# nixie.net
KiCad netlist of a schematic drawn in EAGLE
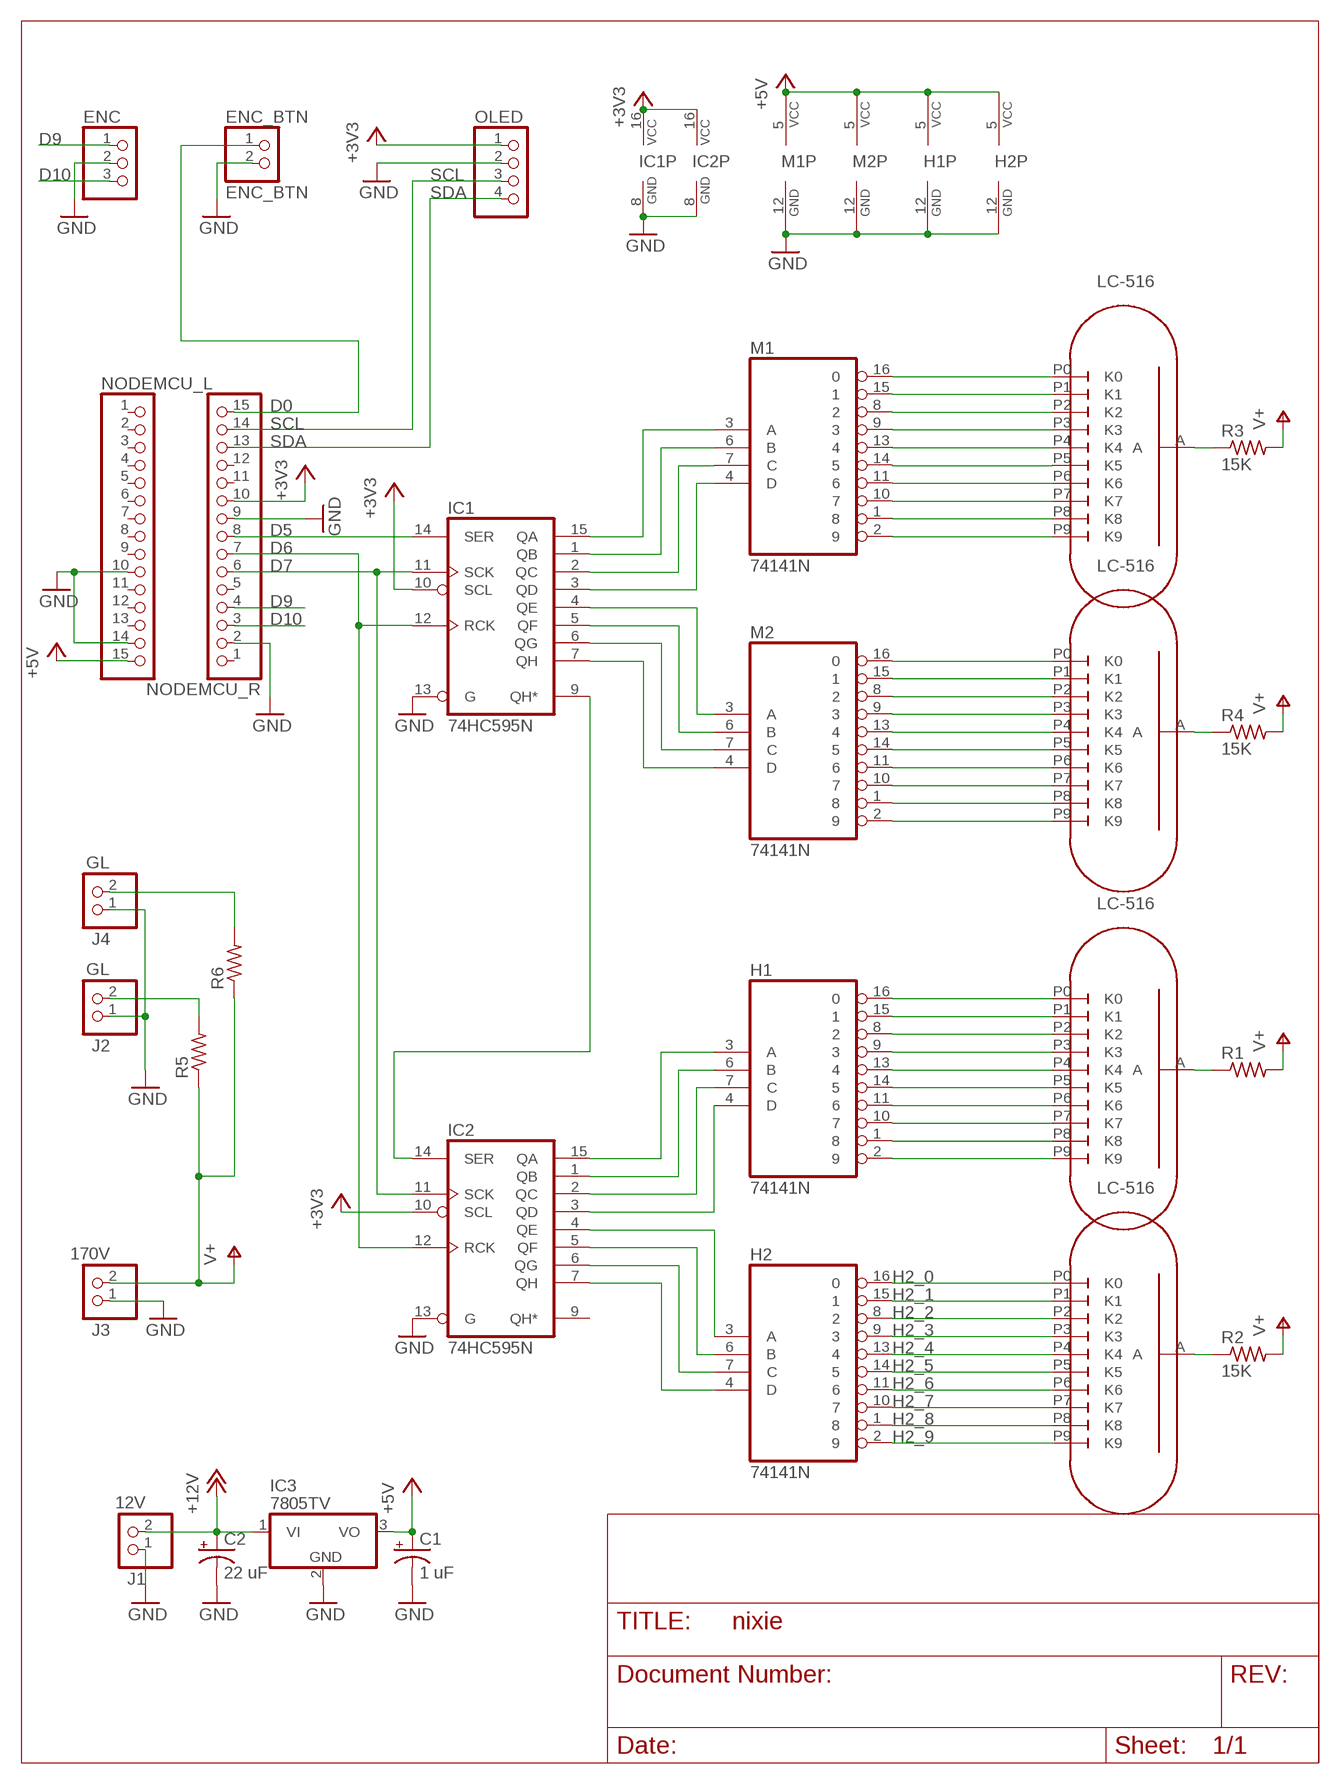
[diagram p0: schematic, sheet 1]

(export (version "E")
  (design (tool "Eeschema 10.0.6"))
  (components
    (comp (ref "C1")
      (value "1 uF")
      (footprint "eagle-import:TT2D5")
      (libsource (lib "eagle-import") (part "CPOL-USTT2D5"))
    )
    (comp (ref "C2")
      (value "22 uF")
      (footprint "eagle-import:TT2D5")
      (libsource (lib "eagle-import") (part "CPOL-USTT2D5"))
    )
    (comp (ref "ENC")
      (value "PINHD-1X3")
      (footprint "eagle-import:1X03")
      (libsource (lib "eagle-import") (part "PINHD-1X3"))
    )
    (comp (ref "ENC_BTN")
      (value "ENC_BTN")
      (footprint "eagle-import:1X02")
      (libsource (lib "eagle-import") (part "PINHD-1X2"))
    )
    (comp (ref "H1")
      (value "74141N")
      (footprint "eagle-import:DIL16")
      (libsource (lib "eagle-import") (part "74141N"))
    )
    (comp (ref "H2")
      (value "74141N")
      (footprint "eagle-import:DIL16")
      (libsource (lib "eagle-import") (part "74141N"))
    )
    (comp (ref "IC1")
      (value "74HC595N")
      (footprint "eagle-import:DIL16")
      (libsource (lib "eagle-import") (part "74595NHC"))
    )
    (comp (ref "IC2")
      (value "74HC595N")
      (footprint "eagle-import:DIL16")
      (libsource (lib "eagle-import") (part "74595NHC"))
    )
    (comp (ref "IC3")
      (value "7805TV")
      (footprint "eagle-import:TO220V")
      (libsource (lib "eagle-import") (part "78TV05"))
    )
    (comp (ref "J1")
      (value "12V")
      (footprint "eagle-import:1X02")
      (libsource (lib "eagle-import") (part "PINHD-1X2"))
    )
    (comp (ref "J2")
      (value "GL")
      (footprint "eagle-import:1X02")
      (libsource (lib "eagle-import") (part "PINHD-1X2"))
    )
    (comp (ref "J3")
      (value "170V")
      (footprint "eagle-import:1X02")
      (libsource (lib "eagle-import") (part "PINHD-1X2"))
    )
    (comp (ref "J4")
      (value "GL")
      (footprint "eagle-import:1X02")
      (libsource (lib "eagle-import") (part "PINHD-1X2"))
    )
    (comp (ref "M1")
      (value "74141N")
      (footprint "eagle-import:DIL16")
      (libsource (lib "eagle-import") (part "74141N"))
    )
    (comp (ref "M2")
      (value "74141N")
      (footprint "eagle-import:DIL16")
      (libsource (lib "eagle-import") (part "74141N"))
    )
    (comp (ref "NODEMCU_L")
      (value "PINHD-1X15")
      (footprint "eagle-import:1X15")
      (libsource (lib "eagle-import") (part "PINHD-1X15"))
    )
    (comp (ref "NODEMCU_R")
      (value "PINHD-1X15")
      (footprint "eagle-import:1X15")
      (libsource (lib "eagle-import") (part "PINHD-1X15"))
    )
    (comp (ref "OLED")
      (value "PINHD-1X4")
      (footprint "eagle-import:1X04")
      (libsource (lib "eagle-import") (part "PINHD-1X4"))
    )
    (comp (ref "R1")
      (value "15K")
      (footprint "eagle-import:0207_10")
      (libsource (lib "eagle-import") (part "R-US_0207/10"))
    )
    (comp (ref "R2")
      (value "15K")
      (footprint "eagle-import:0207_10")
      (libsource (lib "eagle-import") (part "R-US_0207/10"))
    )
    (comp (ref "R3")
      (value "15K")
      (footprint "eagle-import:0207_10")
      (libsource (lib "eagle-import") (part "R-US_0207/10"))
    )
    (comp (ref "R4")
      (value "15K")
      (footprint "eagle-import:0207_10")
      (libsource (lib "eagle-import") (part "R-US_0207/10"))
    )
    (comp (ref "R5")
      (value "100k")
      (footprint "eagle-import:0207_10")
      (libsource (lib "eagle-import") (part "R-US_0207/10"))
    )
    (comp (ref "R6")
      (value "100k")
      (footprint "eagle-import:0207_10")
      (libsource (lib "eagle-import") (part "R-US_0207/10"))
    )
    (comp (ref "U$1M2")
      (value "LC-516")
      (footprint "eagle-import:LC-516")
      (libsource (lib "eagle-import") (part "LC-516"))
    )
    (comp (ref "U$2M1")
      (value "LC-516")
      (footprint "eagle-import:LC-516")
      (libsource (lib "eagle-import") (part "LC-516"))
    )
    (comp (ref "U$3H2")
      (value "LC-516")
      (footprint "eagle-import:LC-516")
      (libsource (lib "eagle-import") (part "LC-516"))
    )
    (comp (ref "U$4H1")
      (value "LC-516")
      (footprint "eagle-import:LC-516")
      (libsource (lib "eagle-import") (part "LC-516"))
    )
  )
  (nets
    (net (code "1") (name "+3V3") (class "Default")
      (node (ref "IC1") (pin "10") (pinfunction "SCL_10") (pintype "input"))
      (node (ref "IC1") (pin "16") (pinfunction "VCC_16") (pintype "power_in"))
      (node (ref "IC2") (pin "10") (pinfunction "SCL_10") (pintype "input"))
      (node (ref "IC2") (pin "16") (pinfunction "VCC_16") (pintype "power_in"))
      (node (ref "NODEMCU_R") (pin "10") (pinfunction "10_10") (pintype "passive"))
      (node (ref "OLED") (pin "1") (pinfunction "1_1") (pintype "passive"))
    )
    (net (code "2") (name "+5V") (class "Default")
      (node (ref "C1") (pin "+") (pinfunction "+_+") (pintype "passive"))
      (node (ref "H1") (pin "5") (pinfunction "VCC_5") (pintype "power_in"))
      (node (ref "H2") (pin "5") (pinfunction "VCC_5") (pintype "power_in"))
      (node (ref "IC3") (pin "3") (pinfunction "VO_3") (pintype "passive"))
      (node (ref "M1") (pin "5") (pinfunction "VCC_5") (pintype "power_in"))
      (node (ref "M2") (pin "5") (pinfunction "VCC_5") (pintype "power_in"))
      (node (ref "NODEMCU_L") (pin "15") (pinfunction "15_15") (pintype "passive"))
    )
    (net (code "3") (name "+12V") (class "Default")
      (node (ref "C2") (pin "+") (pinfunction "+_+") (pintype "passive"))
      (node (ref "IC3") (pin "1") (pinfunction "VI_1") (pintype "input"))
      (node (ref "J1") (pin "2") (pinfunction "2_2") (pintype "passive"))
    )
    (net (code "4") (name "/D0") (class "Default")
      (node (ref "ENC_BTN") (pin "1") (pinfunction "1_1") (pintype "passive"))
      (node (ref "NODEMCU_R") (pin "15") (pinfunction "15_15") (pintype "passive"))
    )
    (net (code "5") (name "/D5") (class "Default")
      (node (ref "IC1") (pin "14") (pinfunction "SER_14") (pintype "input"))
      (node (ref "NODEMCU_R") (pin "8") (pinfunction "8_8") (pintype "passive"))
    )
    (net (code "6") (name "/D6") (class "Default")
      (node (ref "IC1") (pin "12") (pinfunction "RCK_12") (pintype "input"))
      (node (ref "IC2") (pin "12") (pinfunction "RCK_12") (pintype "input"))
      (node (ref "NODEMCU_R") (pin "7") (pinfunction "7_7") (pintype "passive"))
    )
    (net (code "7") (name "/D7") (class "Default")
      (node (ref "IC1") (pin "11") (pinfunction "SCK_11") (pintype "input"))
      (node (ref "IC2") (pin "11") (pinfunction "SCK_11") (pintype "input"))
      (node (ref "NODEMCU_R") (pin "6") (pinfunction "6_6") (pintype "passive"))
    )
    (net (code "8") (name "/D9") (class "Default")
      (node (ref "ENC") (pin "1") (pinfunction "1_1") (pintype "passive"))
      (node (ref "NODEMCU_R") (pin "4") (pinfunction "4_4") (pintype "passive"))
    )
    (net (code "9") (name "/D10") (class "Default")
      (node (ref "ENC") (pin "3") (pinfunction "3_3") (pintype "passive"))
      (node (ref "NODEMCU_R") (pin "3") (pinfunction "3_3") (pintype "passive"))
    )
    (net (code "10") (name "/H2_0") (class "Default")
      (node (ref "H2") (pin "16") (pinfunction "0_16") (pintype "open_collector"))
      (node (ref "U$4H1") (pin "P0") (pinfunction "K0_P0") (pintype "bidirectional"))
    )
    (net (code "11") (name "/H2_1") (class "Default")
      (node (ref "H2") (pin "15") (pinfunction "1_15") (pintype "open_collector"))
      (node (ref "U$4H1") (pin "P1") (pinfunction "K1_P1") (pintype "bidirectional"))
    )
    (net (code "12") (name "/H2_2") (class "Default")
      (node (ref "H2") (pin "8") (pinfunction "2_8") (pintype "open_collector"))
      (node (ref "U$4H1") (pin "P2") (pinfunction "K2_P2") (pintype "bidirectional"))
    )
    (net (code "13") (name "/H2_3") (class "Default")
      (node (ref "H2") (pin "9") (pinfunction "3_9") (pintype "open_collector"))
      (node (ref "U$4H1") (pin "P3") (pinfunction "K3_P3") (pintype "bidirectional"))
    )
    (net (code "14") (name "/H2_4") (class "Default")
      (node (ref "H2") (pin "13") (pinfunction "4_13") (pintype "open_collector"))
      (node (ref "U$4H1") (pin "P4") (pinfunction "K4_P4") (pintype "bidirectional"))
    )
    (net (code "15") (name "/H2_5") (class "Default")
      (node (ref "H2") (pin "14") (pinfunction "5_14") (pintype "open_collector"))
      (node (ref "U$4H1") (pin "P5") (pinfunction "K5_P5") (pintype "bidirectional"))
    )
    (net (code "16") (name "/H2_6") (class "Default")
      (node (ref "H2") (pin "11") (pinfunction "6_11") (pintype "open_collector"))
      (node (ref "U$4H1") (pin "P6") (pinfunction "K6_P6") (pintype "bidirectional"))
    )
    (net (code "17") (name "/H2_7") (class "Default")
      (node (ref "H2") (pin "10") (pinfunction "7_10") (pintype "open_collector"))
      (node (ref "U$4H1") (pin "P7") (pinfunction "K7_P7") (pintype "bidirectional"))
    )
    (net (code "18") (name "/H2_8") (class "Default")
      (node (ref "H2") (pin "1") (pinfunction "8_1") (pintype "open_collector"))
      (node (ref "U$4H1") (pin "P8") (pinfunction "K8_P8") (pintype "bidirectional"))
    )
    (net (code "19") (name "/H2_9") (class "Default")
      (node (ref "H2") (pin "2") (pinfunction "9_2") (pintype "open_collector"))
      (node (ref "U$4H1") (pin "P9") (pinfunction "K9_P9") (pintype "bidirectional"))
    )
    (net (code "20") (name "/SCL") (class "Default")
      (node (ref "NODEMCU_R") (pin "14") (pinfunction "14_14") (pintype "passive"))
      (node (ref "OLED") (pin "3") (pinfunction "3_3") (pintype "passive"))
    )
    (net (code "21") (name "/SDA") (class "Default")
      (node (ref "NODEMCU_R") (pin "13") (pinfunction "13_13") (pintype "passive"))
      (node (ref "OLED") (pin "4") (pinfunction "4_4") (pintype "passive"))
    )
    (net (code "22") (name "GND") (class "Default")
      (node (ref "C1") (pin "-") (pinfunction "-_-") (pintype "passive"))
      (node (ref "C2") (pin "-") (pinfunction "-_-") (pintype "passive"))
      (node (ref "ENC") (pin "2") (pinfunction "2_2") (pintype "passive"))
      (node (ref "ENC_BTN") (pin "2") (pinfunction "2_2") (pintype "passive"))
      (node (ref "H1") (pin "12") (pinfunction "GND_12") (pintype "power_in"))
      (node (ref "H2") (pin "12") (pinfunction "GND_12") (pintype "power_in"))
      (node (ref "IC1") (pin "13") (pinfunction "G_13") (pintype "input"))
      (node (ref "IC1") (pin "8") (pinfunction "GND_8") (pintype "power_in"))
      (node (ref "IC2") (pin "13") (pinfunction "G_13") (pintype "input"))
      (node (ref "IC2") (pin "8") (pinfunction "GND_8") (pintype "power_in"))
      (node (ref "IC3") (pin "2") (pinfunction "GND_2") (pintype "passive"))
      (node (ref "J1") (pin "1") (pinfunction "1_1") (pintype "passive"))
      (node (ref "J2") (pin "1") (pinfunction "1_1") (pintype "passive"))
      (node (ref "J3") (pin "1") (pinfunction "1_1") (pintype "passive"))
      (node (ref "J4") (pin "1") (pinfunction "1_1") (pintype "passive"))
      (node (ref "M1") (pin "12") (pinfunction "GND_12") (pintype "power_in"))
      (node (ref "M2") (pin "12") (pinfunction "GND_12") (pintype "power_in"))
      (node (ref "NODEMCU_L") (pin "10") (pinfunction "10_10") (pintype "passive"))
      (node (ref "NODEMCU_L") (pin "14") (pinfunction "14_14") (pintype "passive"))
      (node (ref "NODEMCU_R") (pin "2") (pinfunction "2_2") (pintype "passive"))
      (node (ref "NODEMCU_R") (pin "9") (pinfunction "9_9") (pintype "passive"))
      (node (ref "OLED") (pin "2") (pinfunction "2_2") (pintype "passive"))
    )
    (net (code "23") (name "Net-(H1A-0)") (class "Default")
      (node (ref "H1") (pin "16") (pinfunction "0_16") (pintype "open_collector"))
      (node (ref "U$3H2") (pin "P0") (pinfunction "K0_P0") (pintype "bidirectional"))
    )
    (net (code "24") (name "Net-(H1A-1)") (class "Default")
      (node (ref "H1") (pin "15") (pinfunction "1_15") (pintype "open_collector"))
      (node (ref "U$3H2") (pin "P1") (pinfunction "K1_P1") (pintype "bidirectional"))
    )
    (net (code "25") (name "Net-(H1A-2)") (class "Default")
      (node (ref "H1") (pin "8") (pinfunction "2_8") (pintype "open_collector"))
      (node (ref "U$3H2") (pin "P2") (pinfunction "K2_P2") (pintype "bidirectional"))
    )
    (net (code "26") (name "Net-(H1A-3)") (class "Default")
      (node (ref "H1") (pin "9") (pinfunction "3_9") (pintype "open_collector"))
      (node (ref "U$3H2") (pin "P3") (pinfunction "K3_P3") (pintype "bidirectional"))
    )
    (net (code "27") (name "Net-(H1A-4)") (class "Default")
      (node (ref "H1") (pin "13") (pinfunction "4_13") (pintype "open_collector"))
      (node (ref "U$3H2") (pin "P4") (pinfunction "K4_P4") (pintype "bidirectional"))
    )
    (net (code "28") (name "Net-(H1A-5)") (class "Default")
      (node (ref "H1") (pin "14") (pinfunction "5_14") (pintype "open_collector"))
      (node (ref "U$3H2") (pin "P5") (pinfunction "K5_P5") (pintype "bidirectional"))
    )
    (net (code "29") (name "Net-(H1A-6)") (class "Default")
      (node (ref "H1") (pin "11") (pinfunction "6_11") (pintype "open_collector"))
      (node (ref "U$3H2") (pin "P6") (pinfunction "K6_P6") (pintype "bidirectional"))
    )
    (net (code "30") (name "Net-(H1A-7)") (class "Default")
      (node (ref "H1") (pin "10") (pinfunction "7_10") (pintype "open_collector"))
      (node (ref "U$3H2") (pin "P7") (pinfunction "K7_P7") (pintype "bidirectional"))
    )
    (net (code "31") (name "Net-(H1A-8)") (class "Default")
      (node (ref "H1") (pin "1") (pinfunction "8_1") (pintype "open_collector"))
      (node (ref "U$3H2") (pin "P8") (pinfunction "K8_P8") (pintype "bidirectional"))
    )
    (net (code "32") (name "Net-(H1A-9)") (class "Default")
      (node (ref "H1") (pin "2") (pinfunction "9_2") (pintype "open_collector"))
      (node (ref "U$3H2") (pin "P9") (pinfunction "K9_P9") (pintype "bidirectional"))
    )
    (net (code "33") (name "Net-(H1A-A)") (class "Default")
      (node (ref "H1") (pin "3") (pinfunction "A_3") (pintype "input"))
      (node (ref "IC2") (pin "15") (pinfunction "QA_15") (pintype "tri_state"))
    )
    (net (code "34") (name "Net-(H1A-B)") (class "Default")
      (node (ref "H1") (pin "6") (pinfunction "B_6") (pintype "input"))
      (node (ref "IC2") (pin "1") (pinfunction "QB_1") (pintype "tri_state"))
    )
    (net (code "35") (name "Net-(H1A-C)") (class "Default")
      (node (ref "H1") (pin "7") (pinfunction "C_7") (pintype "input"))
      (node (ref "IC2") (pin "2") (pinfunction "QC_2") (pintype "tri_state"))
    )
    (net (code "36") (name "Net-(H1A-D)") (class "Default")
      (node (ref "H1") (pin "4") (pinfunction "D_4") (pintype "input"))
      (node (ref "IC2") (pin "3") (pinfunction "QD_3") (pintype "tri_state"))
    )
    (net (code "37") (name "Net-(H2A-A)") (class "Default")
      (node (ref "H2") (pin "3") (pinfunction "A_3") (pintype "input"))
      (node (ref "IC2") (pin "4") (pinfunction "QE_4") (pintype "tri_state"))
    )
    (net (code "38") (name "Net-(H2A-B)") (class "Default")
      (node (ref "H2") (pin "6") (pinfunction "B_6") (pintype "input"))
      (node (ref "IC2") (pin "5") (pinfunction "QF_5") (pintype "tri_state"))
    )
    (net (code "39") (name "Net-(H2A-C)") (class "Default")
      (node (ref "H2") (pin "7") (pinfunction "C_7") (pintype "input"))
      (node (ref "IC2") (pin "6") (pinfunction "QG_6") (pintype "tri_state"))
    )
    (net (code "40") (name "Net-(H2A-D)") (class "Default")
      (node (ref "H2") (pin "4") (pinfunction "D_4") (pintype "input"))
      (node (ref "IC2") (pin "7") (pinfunction "QH_7") (pintype "tri_state"))
    )
    (net (code "41") (name "Net-(IC1A-QA)") (class "Default")
      (node (ref "IC1") (pin "15") (pinfunction "QA_15") (pintype "tri_state"))
      (node (ref "M1") (pin "3") (pinfunction "A_3") (pintype "input"))
    )
    (net (code "42") (name "Net-(IC1A-QB)") (class "Default")
      (node (ref "IC1") (pin "1") (pinfunction "QB_1") (pintype "tri_state"))
      (node (ref "M1") (pin "6") (pinfunction "B_6") (pintype "input"))
    )
    (net (code "43") (name "Net-(IC1A-QC)") (class "Default")
      (node (ref "IC1") (pin "2") (pinfunction "QC_2") (pintype "tri_state"))
      (node (ref "M1") (pin "7") (pinfunction "C_7") (pintype "input"))
    )
    (net (code "44") (name "Net-(IC1A-QD)") (class "Default")
      (node (ref "IC1") (pin "3") (pinfunction "QD_3") (pintype "tri_state"))
      (node (ref "M1") (pin "4") (pinfunction "D_4") (pintype "input"))
    )
    (net (code "45") (name "Net-(IC1A-QE)") (class "Default")
      (node (ref "IC1") (pin "4") (pinfunction "QE_4") (pintype "tri_state"))
      (node (ref "M2") (pin "3") (pinfunction "A_3") (pintype "input"))
    )
    (net (code "46") (name "Net-(IC1A-QF)") (class "Default")
      (node (ref "IC1") (pin "5") (pinfunction "QF_5") (pintype "tri_state"))
      (node (ref "M2") (pin "6") (pinfunction "B_6") (pintype "input"))
    )
    (net (code "47") (name "Net-(IC1A-QG)") (class "Default")
      (node (ref "IC1") (pin "6") (pinfunction "QG_6") (pintype "tri_state"))
      (node (ref "M2") (pin "7") (pinfunction "C_7") (pintype "input"))
    )
    (net (code "48") (name "Net-(IC1A-QH)") (class "Default")
      (node (ref "IC1") (pin "7") (pinfunction "QH_7") (pintype "tri_state"))
      (node (ref "M2") (pin "4") (pinfunction "D_4") (pintype "input"))
    )
    (net (code "49") (name "Net-(IC1A-QH*)") (class "Default")
      (node (ref "IC1") (pin "9") (pinfunction "QH*_9") (pintype "tri_state"))
      (node (ref "IC2") (pin "14") (pinfunction "SER_14") (pintype "input"))
    )
    (net (code "50") (name "Net-(J2-Pad2)") (class "Default")
      (node (ref "J2") (pin "2") (pinfunction "2_2") (pintype "passive"))
      (node (ref "R5") (pin "2") (pinfunction "2_2") (pintype "passive"))
    )
    (net (code "51") (name "Net-(J4-Pad2)") (class "Default")
      (node (ref "J4") (pin "2") (pinfunction "2_2") (pintype "passive"))
      (node (ref "R6") (pin "2") (pinfunction "2_2") (pintype "passive"))
    )
    (net (code "52") (name "Net-(M1A-0)") (class "Default")
      (node (ref "M1") (pin "16") (pinfunction "0_16") (pintype "open_collector"))
      (node (ref "U$1M2") (pin "P0") (pinfunction "K0_P0") (pintype "bidirectional"))
    )
    (net (code "53") (name "Net-(M1A-1)") (class "Default")
      (node (ref "M1") (pin "15") (pinfunction "1_15") (pintype "open_collector"))
      (node (ref "U$1M2") (pin "P1") (pinfunction "K1_P1") (pintype "bidirectional"))
    )
    (net (code "54") (name "Net-(M1A-2)") (class "Default")
      (node (ref "M1") (pin "8") (pinfunction "2_8") (pintype "open_collector"))
      (node (ref "U$1M2") (pin "P2") (pinfunction "K2_P2") (pintype "bidirectional"))
    )
    (net (code "55") (name "Net-(M1A-3)") (class "Default")
      (node (ref "M1") (pin "9") (pinfunction "3_9") (pintype "open_collector"))
      (node (ref "U$1M2") (pin "P3") (pinfunction "K3_P3") (pintype "bidirectional"))
    )
    (net (code "56") (name "Net-(M1A-4)") (class "Default")
      (node (ref "M1") (pin "13") (pinfunction "4_13") (pintype "open_collector"))
      (node (ref "U$1M2") (pin "P4") (pinfunction "K4_P4") (pintype "bidirectional"))
    )
    (net (code "57") (name "Net-(M1A-5)") (class "Default")
      (node (ref "M1") (pin "14") (pinfunction "5_14") (pintype "open_collector"))
      (node (ref "U$1M2") (pin "P5") (pinfunction "K5_P5") (pintype "bidirectional"))
    )
    (net (code "58") (name "Net-(M1A-6)") (class "Default")
      (node (ref "M1") (pin "11") (pinfunction "6_11") (pintype "open_collector"))
      (node (ref "U$1M2") (pin "P6") (pinfunction "K6_P6") (pintype "bidirectional"))
    )
    (net (code "59") (name "Net-(M1A-7)") (class "Default")
      (node (ref "M1") (pin "10") (pinfunction "7_10") (pintype "open_collector"))
      (node (ref "U$1M2") (pin "P7") (pinfunction "K7_P7") (pintype "bidirectional"))
    )
    (net (code "60") (name "Net-(M1A-8)") (class "Default")
      (node (ref "M1") (pin "1") (pinfunction "8_1") (pintype "open_collector"))
      (node (ref "U$1M2") (pin "P8") (pinfunction "K8_P8") (pintype "bidirectional"))
    )
    (net (code "61") (name "Net-(M1A-9)") (class "Default")
      (node (ref "M1") (pin "2") (pinfunction "9_2") (pintype "open_collector"))
      (node (ref "U$1M2") (pin "P9") (pinfunction "K9_P9") (pintype "bidirectional"))
    )
    (net (code "62") (name "Net-(M2A-0)") (class "Default")
      (node (ref "M2") (pin "16") (pinfunction "0_16") (pintype "open_collector"))
      (node (ref "U$2M1") (pin "P0") (pinfunction "K0_P0") (pintype "bidirectional"))
    )
    (net (code "63") (name "Net-(M2A-1)") (class "Default")
      (node (ref "M2") (pin "15") (pinfunction "1_15") (pintype "open_collector"))
      (node (ref "U$2M1") (pin "P1") (pinfunction "K1_P1") (pintype "bidirectional"))
    )
    (net (code "64") (name "Net-(M2A-2)") (class "Default")
      (node (ref "M2") (pin "8") (pinfunction "2_8") (pintype "open_collector"))
      (node (ref "U$2M1") (pin "P2") (pinfunction "K2_P2") (pintype "bidirectional"))
    )
    (net (code "65") (name "Net-(M2A-3)") (class "Default")
      (node (ref "M2") (pin "9") (pinfunction "3_9") (pintype "open_collector"))
      (node (ref "U$2M1") (pin "P3") (pinfunction "K3_P3") (pintype "bidirectional"))
    )
    (net (code "66") (name "Net-(M2A-4)") (class "Default")
      (node (ref "M2") (pin "13") (pinfunction "4_13") (pintype "open_collector"))
      (node (ref "U$2M1") (pin "P4") (pinfunction "K4_P4") (pintype "bidirectional"))
    )
    (net (code "67") (name "Net-(M2A-5)") (class "Default")
      (node (ref "M2") (pin "14") (pinfunction "5_14") (pintype "open_collector"))
      (node (ref "U$2M1") (pin "P5") (pinfunction "K5_P5") (pintype "bidirectional"))
    )
    (net (code "68") (name "Net-(M2A-6)") (class "Default")
      (node (ref "M2") (pin "11") (pinfunction "6_11") (pintype "open_collector"))
      (node (ref "U$2M1") (pin "P6") (pinfunction "K6_P6") (pintype "bidirectional"))
    )
    (net (code "69") (name "Net-(M2A-7)") (class "Default")
      (node (ref "M2") (pin "10") (pinfunction "7_10") (pintype "open_collector"))
      (node (ref "U$2M1") (pin "P7") (pinfunction "K7_P7") (pintype "bidirectional"))
    )
    (net (code "70") (name "Net-(M2A-8)") (class "Default")
      (node (ref "M2") (pin "1") (pinfunction "8_1") (pintype "open_collector"))
      (node (ref "U$2M1") (pin "P8") (pinfunction "K8_P8") (pintype "bidirectional"))
    )
    (net (code "71") (name "Net-(M2A-9)") (class "Default")
      (node (ref "M2") (pin "2") (pinfunction "9_2") (pintype "open_collector"))
      (node (ref "U$2M1") (pin "P9") (pinfunction "K9_P9") (pintype "bidirectional"))
    )
    (net (code "72") (name "Net-(R1-Pad1)") (class "Default")
      (node (ref "R1") (pin "1") (pinfunction "1_1") (pintype "passive"))
      (node (ref "U$3H2") (pin "A") (pinfunction "A_A") (pintype "bidirectional"))
    )
    (net (code "73") (name "Net-(R2-Pad1)") (class "Default")
      (node (ref "R2") (pin "1") (pinfunction "1_1") (pintype "passive"))
      (node (ref "U$4H1") (pin "A") (pinfunction "A_A") (pintype "bidirectional"))
    )
    (net (code "74") (name "Net-(R3-Pad1)") (class "Default")
      (node (ref "R3") (pin "1") (pinfunction "1_1") (pintype "passive"))
      (node (ref "U$1M2") (pin "A") (pinfunction "A_A") (pintype "bidirectional"))
    )
    (net (code "75") (name "Net-(R4-Pad1)") (class "Default")
      (node (ref "R4") (pin "1") (pinfunction "1_1") (pintype "passive"))
      (node (ref "U$2M1") (pin "A") (pinfunction "A_A") (pintype "bidirectional"))
    )
    (net (code "76") (name "V+") (class "Default")
      (node (ref "J3") (pin "2") (pinfunction "2_2") (pintype "passive"))
      (node (ref "R1") (pin "2") (pinfunction "2_2") (pintype "passive"))
      (node (ref "R2") (pin "2") (pinfunction "2_2") (pintype "passive"))
      (node (ref "R3") (pin "2") (pinfunction "2_2") (pintype "passive"))
      (node (ref "R4") (pin "2") (pinfunction "2_2") (pintype "passive"))
      (node (ref "R5") (pin "1") (pinfunction "1_1") (pintype "passive"))
      (node (ref "R6") (pin "1") (pinfunction "1_1") (pintype "passive"))
    )
    (net (code "77") (name "unconnected-(IC2A-QH*-Pad9)") (class "Default")
      (node (ref "IC2") (pin "9") (pinfunction "QH*_9") (pintype "tri_state"))
    )
    (net (code "78") (name "unconnected-(NODEMCU_L-Pad1)") (class "Default")
      (node (ref "NODEMCU_L") (pin "1") (pinfunction "1_1") (pintype "passive"))
    )
    (net (code "79") (name "unconnected-(NODEMCU_L-Pad2)") (class "Default")
      (node (ref "NODEMCU_L") (pin "2") (pinfunction "2_2") (pintype "passive"))
    )
    (net (code "80") (name "unconnected-(NODEMCU_L-Pad3)") (class "Default")
      (node (ref "NODEMCU_L") (pin "3") (pinfunction "3_3") (pintype "passive"))
    )
    (net (code "81") (name "unconnected-(NODEMCU_L-Pad4)") (class "Default")
      (node (ref "NODEMCU_L") (pin "4") (pinfunction "4_4") (pintype "passive"))
    )
    (net (code "82") (name "unconnected-(NODEMCU_L-Pad5)") (class "Default")
      (node (ref "NODEMCU_L") (pin "5") (pinfunction "5_5") (pintype "passive"))
    )
    (net (code "83") (name "unconnected-(NODEMCU_L-Pad6)") (class "Default")
      (node (ref "NODEMCU_L") (pin "6") (pinfunction "6_6") (pintype "passive"))
    )
    (net (code "84") (name "unconnected-(NODEMCU_L-Pad7)") (class "Default")
      (node (ref "NODEMCU_L") (pin "7") (pinfunction "7_7") (pintype "passive"))
    )
    (net (code "85") (name "unconnected-(NODEMCU_L-Pad8)") (class "Default")
      (node (ref "NODEMCU_L") (pin "8") (pinfunction "8_8") (pintype "passive"))
    )
    (net (code "86") (name "unconnected-(NODEMCU_L-Pad9)") (class "Default")
      (node (ref "NODEMCU_L") (pin "9") (pinfunction "9_9") (pintype "passive"))
    )
    (net (code "87") (name "unconnected-(NODEMCU_L-Pad11)") (class "Default")
      (node (ref "NODEMCU_L") (pin "11") (pinfunction "11_11") (pintype "passive"))
    )
    (net (code "88") (name "unconnected-(NODEMCU_L-Pad12)") (class "Default")
      (node (ref "NODEMCU_L") (pin "12") (pinfunction "12_12") (pintype "passive"))
    )
    (net (code "89") (name "unconnected-(NODEMCU_L-Pad13)") (class "Default")
      (node (ref "NODEMCU_L") (pin "13") (pinfunction "13_13") (pintype "passive"))
    )
    (net (code "90") (name "unconnected-(NODEMCU_R-Pad1)") (class "Default")
      (node (ref "NODEMCU_R") (pin "1") (pinfunction "1_1") (pintype "passive"))
    )
    (net (code "91") (name "unconnected-(NODEMCU_R-Pad5)") (class "Default")
      (node (ref "NODEMCU_R") (pin "5") (pinfunction "5_5") (pintype "passive"))
    )
    (net (code "92") (name "unconnected-(NODEMCU_R-Pad11)") (class "Default")
      (node (ref "NODEMCU_R") (pin "11") (pinfunction "11_11") (pintype "passive"))
    )
    (net (code "93") (name "unconnected-(NODEMCU_R-Pad12)") (class "Default")
      (node (ref "NODEMCU_R") (pin "12") (pinfunction "12_12") (pintype "passive"))
    )
  )
)
